# sdram.net
KiCad netlist of a schematic drawn in Altium Designer
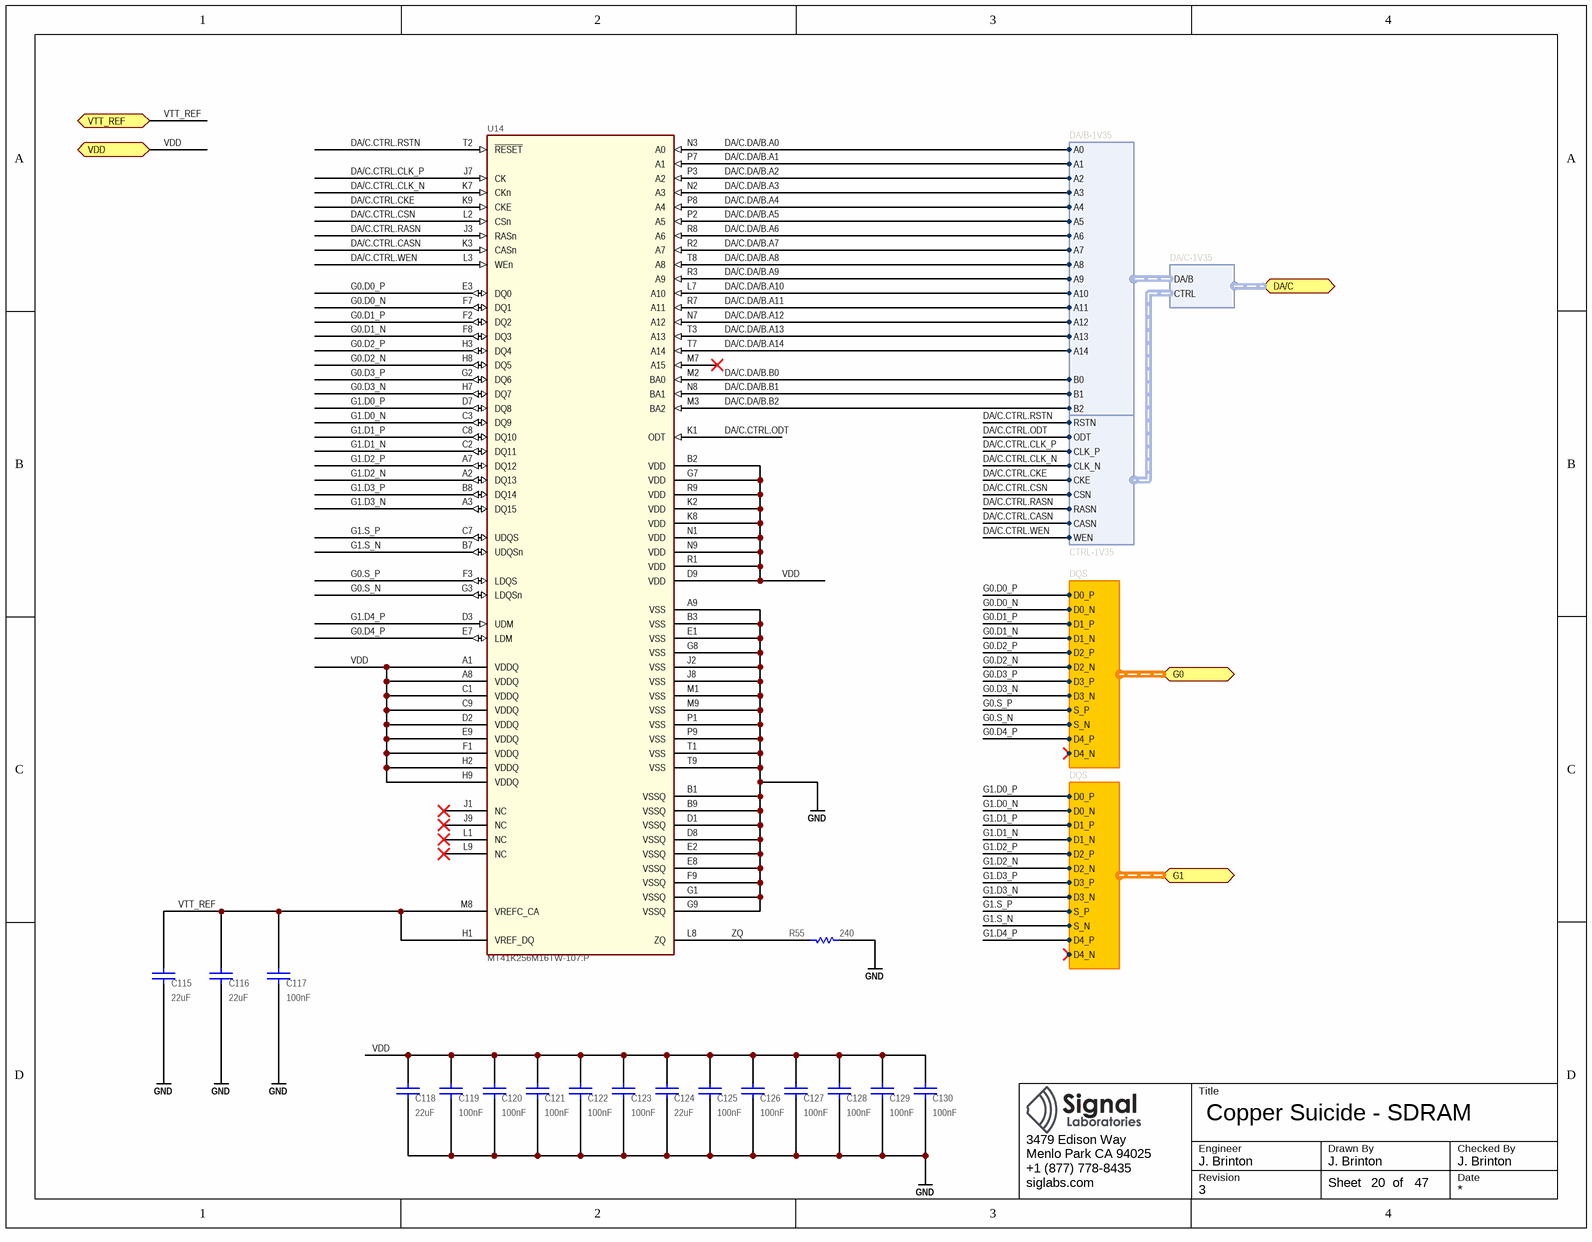
[diagram p0: sdram.SchDoc]

(export (version "E")
  (design (tool "Eeschema 10.0.6"))
  (components
    (comp (ref "C115")
      (value "22uF")
      (footprint "CAPC200X125X145L45N")
      (description "Ceramic Capacitor 22uF ±20% 10V X7S 0805")
      (fields (field (name "MANUFACTURER") "TDK") (field (name "TOLERANCE") "±20%"))
      (libsource (lib "generic") (part "CAP"))
    )
    (comp (ref "C116")
      (value "22uF")
      (footprint "CAPC200X125X145L45N")
      (description "Ceramic Capacitor 22uF ±20% 10V X7S 0805")
      (fields (field (name "MANUFACTURER") "TDK") (field (name "TOLERANCE") "±20%"))
      (libsource (lib "generic") (part "CAP"))
    )
    (comp (ref "C117")
      (value "100nF")
      (footprint "CAPC100X50X55L25N")
      (description "Ceramic Capacitor 100nF ±10% 50V X7R 0402")
      (fields (field (name "MANUFACTURER") "Murata") (field (name "TOLERANCE") "±10%"))
      (libsource (lib "generic") (part "CAP"))
    )
    (comp (ref "C118")
      (value "22uF")
      (footprint "CAPC200X125X145L45N")
      (description "Ceramic Capacitor 22uF ±20% 10V X7S 0805")
      (fields (field (name "MANUFACTURER") "TDK") (field (name "TOLERANCE") "±20%"))
      (libsource (lib "generic") (part "CAP"))
    )
    (comp (ref "C119")
      (value "100nF")
      (footprint "CAPC100X50X55L25N")
      (description "Ceramic Capacitor 100nF ±10% 50V X7R 0402")
      (fields (field (name "MANUFACTURER") "Murata") (field (name "TOLERANCE") "±10%"))
      (libsource (lib "generic") (part "CAP"))
    )
    (comp (ref "C120")
      (value "100nF")
      (footprint "CAPC100X50X55L25N")
      (description "Ceramic Capacitor 100nF ±10% 50V X7R 0402")
      (fields (field (name "MANUFACTURER") "Murata") (field (name "TOLERANCE") "±10%"))
      (libsource (lib "generic") (part "CAP"))
    )
    (comp (ref "C121")
      (value "100nF")
      (footprint "CAPC100X50X55L25N")
      (description "Ceramic Capacitor 100nF ±10% 50V X7R 0402")
      (fields (field (name "MANUFACTURER") "Murata") (field (name "TOLERANCE") "±10%"))
      (libsource (lib "generic") (part "CAP"))
    )
    (comp (ref "C122")
      (value "100nF")
      (footprint "CAPC100X50X55L25N")
      (description "Ceramic Capacitor 100nF ±10% 50V X7R 0402")
      (fields (field (name "MANUFACTURER") "Murata") (field (name "TOLERANCE") "±10%"))
      (libsource (lib "generic") (part "CAP"))
    )
    (comp (ref "C123")
      (value "100nF")
      (footprint "CAPC100X50X55L25N")
      (description "Ceramic Capacitor 100nF ±10% 50V X7R 0402")
      (fields (field (name "MANUFACTURER") "Murata") (field (name "TOLERANCE") "±10%"))
      (libsource (lib "generic") (part "CAP"))
    )
    (comp (ref "C124")
      (value "22uF")
      (footprint "CAPC200X125X145L45N")
      (description "Ceramic Capacitor 22uF ±20% 10V X7S 0805")
      (fields (field (name "MANUFACTURER") "TDK") (field (name "TOLERANCE") "±20%"))
      (libsource (lib "generic") (part "CAP"))
    )
    (comp (ref "C125")
      (value "100nF")
      (footprint "CAPC100X50X55L25N")
      (description "Ceramic Capacitor 100nF ±10% 50V X7R 0402")
      (fields (field (name "MANUFACTURER") "Murata") (field (name "TOLERANCE") "±10%"))
      (libsource (lib "generic") (part "CAP"))
    )
    (comp (ref "C126")
      (value "100nF")
      (footprint "CAPC100X50X55L25N")
      (description "Ceramic Capacitor 100nF ±10% 50V X7R 0402")
      (fields (field (name "MANUFACTURER") "Murata") (field (name "TOLERANCE") "±10%"))
      (libsource (lib "generic") (part "CAP"))
    )
    (comp (ref "C127")
      (value "100nF")
      (footprint "CAPC100X50X55L25N")
      (description "Ceramic Capacitor 100nF ±10% 50V X7R 0402")
      (fields (field (name "MANUFACTURER") "Murata") (field (name "TOLERANCE") "±10%"))
      (libsource (lib "generic") (part "CAP"))
    )
    (comp (ref "C128")
      (value "100nF")
      (footprint "CAPC100X50X55L25N")
      (description "Ceramic Capacitor 100nF ±10% 50V X7R 0402")
      (fields (field (name "MANUFACTURER") "Murata") (field (name "TOLERANCE") "±10%"))
      (libsource (lib "generic") (part "CAP"))
    )
    (comp (ref "C129")
      (value "100nF")
      (footprint "CAPC100X50X55L25N")
      (description "Ceramic Capacitor 100nF ±10% 50V X7R 0402")
      (fields (field (name "MANUFACTURER") "Murata") (field (name "TOLERANCE") "±10%"))
      (libsource (lib "generic") (part "CAP"))
    )
    (comp (ref "C130")
      (value "100nF")
      (footprint "CAPC100X50X55L25N")
      (description "Ceramic Capacitor 100nF ±10% 50V X7R 0402")
      (fields (field (name "MANUFACTURER") "Murata") (field (name "TOLERANCE") "±10%"))
      (libsource (lib "generic") (part "CAP"))
    )
    (comp (ref "R55")
      (value "240")
      (footprint "RESC1005X40N")
      (description "Thick Film Resistor 240 ±1% 0.1W 75V 0402")
      (fields (field (name "TOLERANCE") "±1%") (field (name "MANUFACTURER") "Panasonic"))
      (libsource (lib "generic") (part "RES"))
    )
    (comp (ref "U14")
      (value "MT41K256M16TW-107:P")
      (footprint "MT41K256M16TW-107:P")
      (description "DDR3L SDRAM 4Gb (32Megx16bitx8banks)")
      (fields (field (name "MANUFACTURER") "Micron Technology"))
      (libsource (lib "BEAGLEBONEBLACK_REV A5B") (part "MT41K256M16HA"))
    )
  )
  (nets
    (net (code "5") (name "/DA{slash}C.CTRL.CASN") (class "Default")
      (node (ref "U14") (pin "K3") (pinfunction "CASn_K3") (pintype "input"))
    )
    (net (code "6") (name "/DA{slash}C.CTRL.CKE") (class "Default")
      (node (ref "U14") (pin "K9") (pinfunction "CKE_K9") (pintype "input"))
    )
    (net (code "7") (name "/DA{slash}C.CTRL.CLK_N") (class "Default")
      (node (ref "U14") (pin "K7") (pinfunction "CKn_K7") (pintype "input"))
    )
    (net (code "8") (name "/DA{slash}C.CTRL.CLK_P") (class "Default")
      (node (ref "U14") (pin "J7") (pinfunction "CK_J7") (pintype "input"))
    )
    (net (code "9") (name "/DA{slash}C.CTRL.CSN") (class "Default")
      (node (ref "U14") (pin "L2") (pinfunction "CSn_L2") (pintype "input"))
    )
    (net (code "10") (name "/DA{slash}C.CTRL.ODT") (class "Default")
      (node (ref "U14") (pin "K1") (pinfunction "ODT_K1") (pintype "input"))
    )
    (net (code "11") (name "/DA{slash}C.CTRL.RASN") (class "Default")
      (node (ref "U14") (pin "J3") (pinfunction "RASn_J3") (pintype "input"))
    )
    (net (code "12") (name "/DA{slash}C.CTRL.RSTN") (class "Default")
      (node (ref "U14") (pin "T2") (pinfunction "~{RESET}_T2") (pintype "input"))
    )
    (net (code "13") (name "/DA{slash}C.CTRL.WEN") (class "Default")
      (node (ref "U14") (pin "L3") (pinfunction "WEn_L3") (pintype "input"))
    )
    (net (code "14") (name "/DA{slash}C.DA{slash}B.A0") (class "Default")
      (node (ref "U14") (pin "N3") (pinfunction "A0_N3") (pintype "input"))
    )
    (net (code "15") (name "/DA{slash}C.DA{slash}B.A1") (class "Default")
      (node (ref "U14") (pin "P7") (pinfunction "A1_P7") (pintype "input"))
    )
    (net (code "16") (name "/DA{slash}C.DA{slash}B.A2") (class "Default")
      (node (ref "U14") (pin "P3") (pinfunction "A2_P3") (pintype "input"))
    )
    (net (code "17") (name "/DA{slash}C.DA{slash}B.A3") (class "Default")
      (node (ref "U14") (pin "N2") (pinfunction "A3_N2") (pintype "input"))
    )
    (net (code "18") (name "/DA{slash}C.DA{slash}B.A4") (class "Default")
      (node (ref "U14") (pin "P8") (pinfunction "A4_P8") (pintype "input"))
    )
    (net (code "19") (name "/DA{slash}C.DA{slash}B.A5") (class "Default")
      (node (ref "U14") (pin "P2") (pinfunction "A5_P2") (pintype "input"))
    )
    (net (code "20") (name "/DA{slash}C.DA{slash}B.A6") (class "Default")
      (node (ref "U14") (pin "R8") (pinfunction "A6_R8") (pintype "input"))
    )
    (net (code "21") (name "/DA{slash}C.DA{slash}B.A7") (class "Default")
      (node (ref "U14") (pin "R2") (pinfunction "A7_R2") (pintype "input"))
    )
    (net (code "22") (name "/DA{slash}C.DA{slash}B.A8") (class "Default")
      (node (ref "U14") (pin "T8") (pinfunction "A8_T8") (pintype "input"))
    )
    (net (code "23") (name "/DA{slash}C.DA{slash}B.A9") (class "Default")
      (node (ref "U14") (pin "R3") (pinfunction "A9_R3") (pintype "input"))
    )
    (net (code "24") (name "/DA{slash}C.DA{slash}B.A10") (class "Default")
      (node (ref "U14") (pin "L7") (pinfunction "A10_L7") (pintype "input"))
    )
    (net (code "25") (name "/DA{slash}C.DA{slash}B.A11") (class "Default")
      (node (ref "U14") (pin "R7") (pinfunction "A11_R7") (pintype "input"))
    )
    (net (code "26") (name "/DA{slash}C.DA{slash}B.A12") (class "Default")
      (node (ref "U14") (pin "N7") (pinfunction "A12_N7") (pintype "input"))
    )
    (net (code "27") (name "/DA{slash}C.DA{slash}B.A13") (class "Default")
      (node (ref "U14") (pin "T3") (pinfunction "A13_T3") (pintype "input"))
    )
    (net (code "28") (name "/DA{slash}C.DA{slash}B.A14") (class "Default")
      (node (ref "U14") (pin "T7") (pinfunction "A14_T7") (pintype "input"))
    )
    (net (code "29") (name "/DA{slash}C.DA{slash}B.B0") (class "Default")
      (node (ref "U14") (pin "M2") (pinfunction "BA0_M2") (pintype "input"))
    )
    (net (code "30") (name "/DA{slash}C.DA{slash}B.B1") (class "Default")
      (node (ref "U14") (pin "N8") (pinfunction "BA1_N8") (pintype "input"))
    )
    (net (code "31") (name "/DA{slash}C.DA{slash}B.B2") (class "Default")
      (node (ref "U14") (pin "M3") (pinfunction "BA2_M3") (pintype "input"))
    )
    (net (code "33") (name "/G0.D0_N") (class "Default")
      (node (ref "U14") (pin "F7") (pinfunction "DQ1_F7") (pintype "bidirectional"))
    )
    (net (code "34") (name "/G0.D0_P") (class "Default")
      (node (ref "U14") (pin "E3") (pinfunction "DQ0_E3") (pintype "bidirectional"))
    )
    (net (code "35") (name "/G0.D1_N") (class "Default")
      (node (ref "U14") (pin "F8") (pinfunction "DQ3_F8") (pintype "bidirectional"))
    )
    (net (code "36") (name "/G0.D1_P") (class "Default")
      (node (ref "U14") (pin "F2") (pinfunction "DQ2_F2") (pintype "bidirectional"))
    )
    (net (code "37") (name "/G0.D2_N") (class "Default")
      (node (ref "U14") (pin "H8") (pinfunction "DQ5_H8") (pintype "bidirectional"))
    )
    (net (code "38") (name "/G0.D2_P") (class "Default")
      (node (ref "U14") (pin "H3") (pinfunction "DQ4_H3") (pintype "bidirectional"))
    )
    (net (code "39") (name "/G0.D3_N") (class "Default")
      (node (ref "U14") (pin "H7") (pinfunction "DQ7_H7") (pintype "bidirectional"))
    )
    (net (code "40") (name "/G0.D3_P") (class "Default")
      (node (ref "U14") (pin "G2") (pinfunction "DQ6_G2") (pintype "bidirectional"))
    )
    (net (code "41") (name "/G0.D4_P") (class "Default")
      (node (ref "U14") (pin "E7") (pinfunction "LDM_E7") (pintype "bidirectional"))
    )
    (net (code "42") (name "/G0.S_N") (class "Default")
      (node (ref "U14") (pin "G3") (pinfunction "LDQSn_G3") (pintype "bidirectional"))
    )
    (net (code "43") (name "/G0.S_P") (class "Default")
      (node (ref "U14") (pin "F3") (pinfunction "LDQS_F3") (pintype "bidirectional"))
    )
    (net (code "44") (name "/G1.D0_N") (class "Default")
      (node (ref "U14") (pin "C3") (pinfunction "DQ9_C3") (pintype "bidirectional"))
    )
    (net (code "45") (name "/G1.D0_P") (class "Default")
      (node (ref "U14") (pin "D7") (pinfunction "DQ8_D7") (pintype "bidirectional"))
    )
    (net (code "46") (name "/G1.D1_N") (class "Default")
      (node (ref "U14") (pin "C2") (pinfunction "DQ11_C2") (pintype "bidirectional"))
    )
    (net (code "47") (name "/G1.D1_P") (class "Default")
      (node (ref "U14") (pin "C8") (pinfunction "DQ10_C8") (pintype "bidirectional"))
    )
    (net (code "48") (name "/G1.D2_N") (class "Default")
      (node (ref "U14") (pin "A2") (pinfunction "DQ13_A2") (pintype "bidirectional"))
    )
    (net (code "49") (name "/G1.D2_P") (class "Default")
      (node (ref "U14") (pin "A7") (pinfunction "DQ12_A7") (pintype "bidirectional"))
    )
    (net (code "50") (name "/G1.D3_N") (class "Default")
      (node (ref "U14") (pin "A3") (pinfunction "DQ15_A3") (pintype "bidirectional"))
    )
    (net (code "51") (name "/G1.D3_P") (class "Default")
      (node (ref "U14") (pin "B8") (pinfunction "DQ14_B8") (pintype "bidirectional"))
    )
    (net (code "52") (name "/G1.D4_P") (class "Default")
      (node (ref "U14") (pin "D3") (pinfunction "UDM_D3") (pintype "input"))
    )
    (net (code "53") (name "/G1.S_N") (class "Default")
      (node (ref "U14") (pin "B7") (pinfunction "UDQSn_B7") (pintype "bidirectional"))
    )
    (net (code "54") (name "/G1.S_P") (class "Default")
      (node (ref "U14") (pin "C7") (pinfunction "UDQS_C7") (pintype "bidirectional"))
    )
    (net (code "55") (name "/VDD") (class "Default")
      (node (ref "C118") (pin "1") (pinfunction "1_1") (pintype "passive"))
      (node (ref "C119") (pin "2") (pinfunction "2_2") (pintype "passive"))
      (node (ref "C120") (pin "2") (pinfunction "2_2") (pintype "passive"))
      (node (ref "C121") (pin "2") (pinfunction "2_2") (pintype "passive"))
      (node (ref "C122") (pin "2") (pinfunction "2_2") (pintype "passive"))
      (node (ref "C123") (pin "2") (pinfunction "2_2") (pintype "passive"))
      (node (ref "C124") (pin "1") (pinfunction "1_1") (pintype "passive"))
      (node (ref "C125") (pin "2") (pinfunction "2_2") (pintype "passive"))
      (node (ref "C126") (pin "2") (pinfunction "2_2") (pintype "passive"))
      (node (ref "C127") (pin "2") (pinfunction "2_2") (pintype "passive"))
      (node (ref "C128") (pin "2") (pinfunction "2_2") (pintype "passive"))
      (node (ref "C129") (pin "2") (pinfunction "2_2") (pintype "passive"))
      (node (ref "C130") (pin "2") (pinfunction "2_2") (pintype "passive"))
      (node (ref "U14") (pin "A1") (pinfunction "VDDQ_A1") (pintype "power_in"))
      (node (ref "U14") (pin "A8") (pinfunction "VDDQ_A8") (pintype "power_in"))
      (node (ref "U14") (pin "B2") (pinfunction "VDD_B2") (pintype "power_in"))
      (node (ref "U14") (pin "C1") (pinfunction "VDDQ_C1") (pintype "power_in"))
      (node (ref "U14") (pin "C9") (pinfunction "VDDQ_C9") (pintype "power_in"))
      (node (ref "U14") (pin "D2") (pinfunction "VDDQ_D2") (pintype "power_in"))
      (node (ref "U14") (pin "D9") (pinfunction "VDD_D9") (pintype "power_in"))
      (node (ref "U14") (pin "E9") (pinfunction "VDDQ_E9") (pintype "power_in"))
      (node (ref "U14") (pin "F1") (pinfunction "VDDQ_F1") (pintype "power_in"))
      (node (ref "U14") (pin "G7") (pinfunction "VDD_G7") (pintype "power_in"))
      (node (ref "U14") (pin "H2") (pinfunction "VDDQ_H2") (pintype "power_in"))
      (node (ref "U14") (pin "H9") (pinfunction "VDDQ_H9") (pintype "power_in"))
      (node (ref "U14") (pin "K2") (pinfunction "VDD_K2") (pintype "power_in"))
      (node (ref "U14") (pin "K8") (pinfunction "VDD_K8") (pintype "power_in"))
      (node (ref "U14") (pin "N1") (pinfunction "VDD_N1") (pintype "power_in"))
      (node (ref "U14") (pin "N9") (pinfunction "VDD_N9") (pintype "power_in"))
      (node (ref "U14") (pin "R1") (pinfunction "VDD_R1") (pintype "power_in"))
      (node (ref "U14") (pin "R9") (pinfunction "VDD_R9") (pintype "power_in"))
    )
    (net (code "56") (name "/VTT_REF") (class "Default")
      (node (ref "C115") (pin "1") (pinfunction "1_1") (pintype "passive"))
      (node (ref "C116") (pin "1") (pinfunction "1_1") (pintype "passive"))
      (node (ref "C117") (pin "2") (pinfunction "2_2") (pintype "passive"))
      (node (ref "U14") (pin "H1") (pinfunction "VREF_DQ_H1") (pintype "passive"))
      (node (ref "U14") (pin "M8") (pinfunction "VREFC_CA_M8") (pintype "power_in"))
    )
    (net (code "57") (name "/ZQ") (class "Default")
      (node (ref "R55") (pin "2") (pinfunction "2_2") (pintype "passive"))
      (node (ref "U14") (pin "L8") (pinfunction "ZQ_L8") (pintype "passive"))
    )
    (net (code "61") (name "GND") (class "Default")
      (node (ref "C115") (pin "2") (pinfunction "2_2") (pintype "passive"))
      (node (ref "C116") (pin "2") (pinfunction "2_2") (pintype "passive"))
      (node (ref "C117") (pin "1") (pinfunction "1_1") (pintype "passive"))
      (node (ref "C118") (pin "2") (pinfunction "2_2") (pintype "passive"))
      (node (ref "C119") (pin "1") (pinfunction "1_1") (pintype "passive"))
      (node (ref "C120") (pin "1") (pinfunction "1_1") (pintype "passive"))
      (node (ref "C121") (pin "1") (pinfunction "1_1") (pintype "passive"))
      (node (ref "C122") (pin "1") (pinfunction "1_1") (pintype "passive"))
      (node (ref "C123") (pin "1") (pinfunction "1_1") (pintype "passive"))
      (node (ref "C124") (pin "2") (pinfunction "2_2") (pintype "passive"))
      (node (ref "C125") (pin "1") (pinfunction "1_1") (pintype "passive"))
      (node (ref "C126") (pin "1") (pinfunction "1_1") (pintype "passive"))
      (node (ref "C127") (pin "1") (pinfunction "1_1") (pintype "passive"))
      (node (ref "C128") (pin "1") (pinfunction "1_1") (pintype "passive"))
      (node (ref "C129") (pin "1") (pinfunction "1_1") (pintype "passive"))
      (node (ref "C130") (pin "1") (pinfunction "1_1") (pintype "passive"))
      (node (ref "R55") (pin "1") (pinfunction "1_1") (pintype "passive"))
      (node (ref "U14") (pin "A9") (pinfunction "VSS_A9") (pintype "power_in"))
      (node (ref "U14") (pin "B1") (pinfunction "VSSQ_B1") (pintype "power_in"))
      (node (ref "U14") (pin "B3") (pinfunction "VSS_B3") (pintype "power_in"))
      (node (ref "U14") (pin "B9") (pinfunction "VSSQ_B9") (pintype "power_in"))
      (node (ref "U14") (pin "D1") (pinfunction "VSSQ_D1") (pintype "power_in"))
      (node (ref "U14") (pin "D8") (pinfunction "VSSQ_D8") (pintype "power_in"))
      (node (ref "U14") (pin "E1") (pinfunction "VSS_E1") (pintype "power_in"))
      (node (ref "U14") (pin "E2") (pinfunction "VSSQ_E2") (pintype "power_in"))
      (node (ref "U14") (pin "E8") (pinfunction "VSSQ_E8") (pintype "power_in"))
      (node (ref "U14") (pin "F9") (pinfunction "VSSQ_F9") (pintype "power_in"))
      (node (ref "U14") (pin "G1") (pinfunction "VSSQ_G1") (pintype "power_in"))
      (node (ref "U14") (pin "G8") (pinfunction "VSS_G8") (pintype "power_in"))
      (node (ref "U14") (pin "G9") (pinfunction "VSSQ_G9") (pintype "power_in"))
      (node (ref "U14") (pin "J2") (pinfunction "VSS_J2") (pintype "power_in"))
      (node (ref "U14") (pin "J8") (pinfunction "VSS_J8") (pintype "power_in"))
      (node (ref "U14") (pin "M1") (pinfunction "VSS_M1") (pintype "power_in"))
      (node (ref "U14") (pin "M9") (pinfunction "VSS_M9") (pintype "power_in"))
      (node (ref "U14") (pin "P1") (pinfunction "VSS_P1") (pintype "power_in"))
      (node (ref "U14") (pin "P9") (pinfunction "VSS_P9") (pintype "power_in"))
      (node (ref "U14") (pin "T1") (pinfunction "VSS_T1") (pintype "power_in"))
      (node (ref "U14") (pin "T9") (pinfunction "VSS_T9") (pintype "power_in"))
    )
    (net (code "62") (name "unconnected-(U14-A15-PadM7)") (class "Default")
      (node (ref "U14") (pin "M7") (pinfunction "A15_M7") (pintype "input+no_connect"))
    )
    (net (code "63") (name "unconnected-(U14-NC-PadJ1)") (class "Default")
      (node (ref "U14") (pin "J1") (pinfunction "NC_J1") (pintype "passive+no_connect"))
    )
    (net (code "64") (name "unconnected-(U14-NC-PadJ9)") (class "Default")
      (node (ref "U14") (pin "J9") (pinfunction "NC_J9") (pintype "passive+no_connect"))
    )
    (net (code "65") (name "unconnected-(U14-NC-PadL1)") (class "Default")
      (node (ref "U14") (pin "L1") (pinfunction "NC_L1") (pintype "power_in+no_connect"))
    )
    (net (code "66") (name "unconnected-(U14-NC-PadL9)") (class "Default")
      (node (ref "U14") (pin "L9") (pinfunction "NC_L9") (pintype "power_in+no_connect"))
    )
  )
)
